# boost.net
KiCad netlist of a schematic drawn in Altium Designer
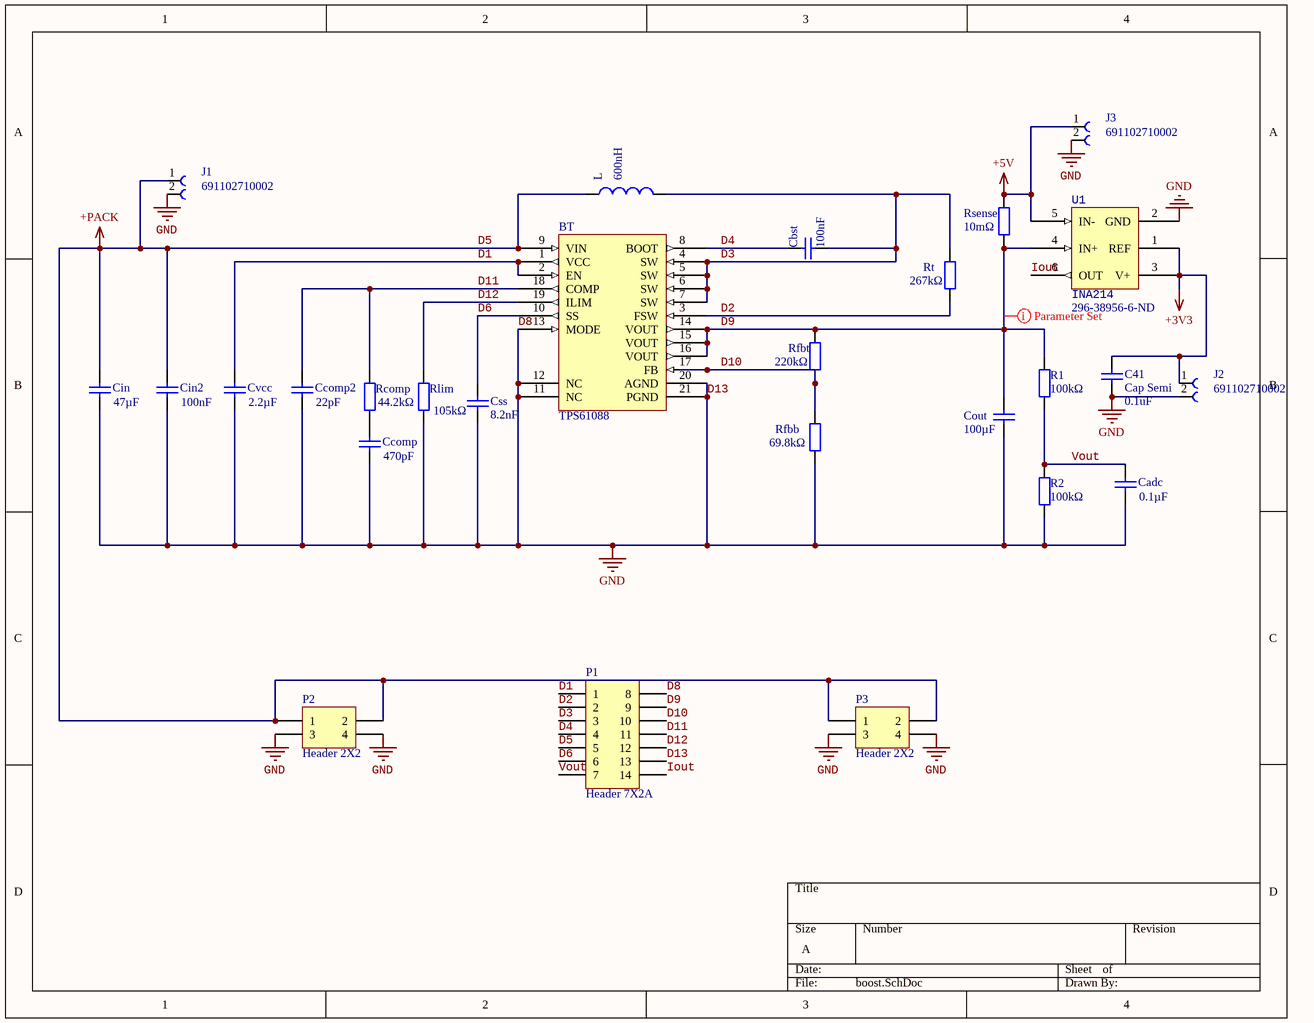
[diagram p0: boost.SchDoc]

(export (version "E")
  (design (tool "Eeschema 10.0.6"))
  (components
    (comp (ref "BT")
      (value "TPS61088")
      (footprint "QFN50P450X350X100-21N")
      (description "Boost converter")
      (libsource (lib "heron-general") (part "TPS61088"))
    )
    (comp (ref "C41")
      (value "Cap Semi")
      (footprint "1608[0603]")
      (description "Capacitor (Semiconductor SIM Model)")
      (fields (field (name "ALTIUM_VALUE") "0.1uF") (field (name "PUBLISHER") "Altium Limited"))
      (libsource (lib "Miscellaneous Devices") (part "Cap Semi"))
    )
    (comp (ref "Cadc")
      (value "0.1µF")
      (footprint "1608[0603]")
      (description "Capacitor")
      (fields (field (name "PUBLISHER") "Altium Limited"))
      (libsource (lib "Miscellaneous Devices") (part "Cap"))
    )
    (comp (ref "Cbst")
      (value "100nF")
      (footprint "1608[0603]")
      (description "Capacitor")
      (fields (field (name "PUBLISHER") "Altium Limited"))
      (libsource (lib "Miscellaneous Devices") (part "Cap"))
    )
    (comp (ref "Ccomp")
      (value "470pF")
      (footprint "1608[0603]")
      (description "Capacitor")
      (fields (field (name "PUBLISHER") "Altium Limited"))
      (libsource (lib "Miscellaneous Devices") (part "Cap"))
    )
    (comp (ref "Ccomp2")
      (value "22pF")
      (footprint "0805")
      (description "Capacitor")
      (fields (field (name "PUBLISHER") "Altium Limited"))
      (libsource (lib "Miscellaneous Devices") (part "Cap"))
    )
    (comp (ref "Cin")
      (value "47µF")
      (footprint "1608[0603]")
      (description "Capacitor")
      (fields (field (name "PUBLISHER") "Altium Limited"))
      (libsource (lib "Miscellaneous Devices") (part "Cap"))
    )
    (comp (ref "Cin2")
      (value "100nF")
      (footprint "1608[0603]")
      (description "Capacitor")
      (fields (field (name "PUBLISHER") "Altium Limited"))
      (libsource (lib "Miscellaneous Devices") (part "Cap"))
    )
    (comp (ref "Cout")
      (value "100µF")
      (footprint "1210")
      (description "Capacitor")
      (fields (field (name "PUBLISHER") "Altium Limited"))
      (libsource (lib "Miscellaneous Devices") (part "Cap"))
    )
    (comp (ref "Css")
      (value "8.2nF")
      (footprint "0805")
      (description "Capacitor")
      (fields (field (name "PUBLISHER") "Altium Limited"))
      (libsource (lib "Miscellaneous Devices") (part "Cap"))
    )
    (comp (ref "Cvcc")
      (value "2.2µF")
      (footprint "0805")
      (description "Capacitor")
      (fields (field (name "PUBLISHER") "Altium Limited"))
      (libsource (lib "Miscellaneous Devices") (part "Cap"))
    )
    (comp (ref "J1")
      (value "691102710002")
      (footprint "691102710002:691102710002")
      (description "102 Series 5mm Pitch Straight, PCB Terminal Block, Through Hole, 2 Way")
      (fields (field (name "MF") "Wurth Electronics"))
      (libsource (lib "691102710002") (part "691102710002"))
    )
    (comp (ref "J2")
      (value "691102710002")
      (footprint "691102710002:691102710002")
      (description "102 Series 5mm Pitch Straight, PCB Terminal Block, Through Hole, 2 Way")
      (fields (field (name "MF") "Wurth Electronics"))
      (libsource (lib "691102710002") (part "691102710002"))
    )
    (comp (ref "J3")
      (value "691102710002")
      (footprint "691102710002:691102710002")
      (description "102 Series 5mm Pitch Straight, PCB Terminal Block, Through Hole, 2 Way")
      (fields (field (name "MF") "Wurth Electronics"))
      (libsource (lib "691102710002") (part "691102710002"))
    )
    (comp (ref "L")
      (value "600nH")
      (footprint "2-SMD")
      (description "Inductor")
      (fields (field (name "PUBLISHER") "Altium Limited"))
      (libsource (lib "Miscellaneous Devices") (part "Inductor"))
    )
    (comp (ref "P1")
      (value "Header 7X2A")
      (footprint "HDR2X7_CEN")
      (description "Header, 7-Pin, Dual row")
      (fields (field (name "PUBLISHER") "Altium Limited"))
      (libsource (lib "Miscellaneous Connectors") (part "Header 7X2A"))
    )
    (comp (ref "P2")
      (value "Header 2X2")
      (footprint "HDR2X2")
      (description "Header, 2-Pin, Dual row")
      (fields (field (name "PUBLISHER") "Altium Limited"))
      (libsource (lib "Miscellaneous Connectors") (part "Header 2X2"))
    )
    (comp (ref "P3")
      (value "Header 2X2")
      (footprint "HDR2X2")
      (description "Header, 2-Pin, Dual row")
      (fields (field (name "PUBLISHER") "Altium Limited"))
      (libsource (lib "Miscellaneous Connectors") (part "Header 2X2"))
    )
    (comp (ref "R1")
      (value "100kΩ")
      (footprint "1608[0603]")
      (description "Resistor")
      (fields (field (name "PUBLISHER") "Altium Limited"))
      (libsource (lib "Miscellaneous Devices") (part "Res2"))
    )
    (comp (ref "R2")
      (value "100kΩ")
      (footprint "1608[0603]")
      (description "Resistor")
      (fields (field (name "PUBLISHER") "Altium Limited"))
      (libsource (lib "Miscellaneous Devices") (part "Res2"))
    )
    (comp (ref "Rcomp")
      (value "44.2kΩ")
      (footprint "0805")
      (description "Resistor")
      (fields (field (name "PUBLISHER") "Altium Limited"))
      (libsource (lib "Miscellaneous Devices") (part "Res2"))
    )
    (comp (ref "Rfbb")
      (value "69.8kΩ")
      (footprint "0805")
      (description "Resistor")
      (fields (field (name "PUBLISHER") "Altium Limited"))
      (libsource (lib "Miscellaneous Devices") (part "Res2"))
    )
    (comp (ref "Rfbt")
      (value "220kΩ")
      (footprint "0805")
      (description "Resistor")
      (fields (field (name "PUBLISHER") "Altium Limited"))
      (libsource (lib "Miscellaneous Devices") (part "Res2"))
    )
    (comp (ref "Rlim")
      (value "105kΩ")
      (footprint "1608[0603]")
      (description "Resistor")
      (fields (field (name "PUBLISHER") "Altium Limited"))
      (libsource (lib "Miscellaneous Devices") (part "Res2"))
    )
    (comp (ref "Rsense")
      (value "10mΩ")
      (footprint "0805")
      (description "Resistor")
      (fields (field (name "Comment") "10mΩ 1/2W 0805") (field (name "PUBLISHER") "Altium Limited"))
      (libsource (lib "Miscellaneous Devices") (part "Res2"))
    )
    (comp (ref "Rt")
      (value "267kΩ")
      (footprint "1608[0603]")
      (description "Resistor")
      (fields (field (name "Comment") "RtA1") (field (name "PUBLISHER") "Altium Limited"))
      (libsource (lib "") (part "Res2_1"))
    )
    (comp (ref "U1")
      (value "INA214")
      (footprint "SOT65P210X110-6N")
      (description "Current monitor")
      (fields (field (name "SUPPLIER PART NUMBER 1") "296-38956-6-ND"))
      (libsource (lib "heron-general") (part "INA214"))
    )
  )
  (nets
    (net (code "1") (name "+3V3") (class "Default")
      (node (ref "C41") (pin "2") (pinfunction "2_2") (pintype "passive"))
      (node (ref "J2") (pin "1") (pinfunction "1_1") (pintype "passive"))
      (node (ref "U1") (pin "1") (pinfunction "REF_1") (pintype "passive"))
      (node (ref "U1") (pin "3") (pinfunction "V+_3") (pintype "power_in"))
    )
    (net (code "2") (name "+5V") (class "Default")
      (node (ref "J3") (pin "1") (pinfunction "1_1") (pintype "passive"))
      (node (ref "Rsense") (pin "2") (pinfunction "2_2") (pintype "passive"))
      (node (ref "U1") (pin "5") (pinfunction "IN-_5") (pintype "input"))
    )
    (net (code "3") (name "+PACK") (class "Default")
      (node (ref "BT") (pin "9") (pinfunction "VIN_9") (pintype "input"))
      (node (ref "Cin") (pin "2") (pinfunction "2_2") (pintype "passive"))
      (node (ref "Cin2") (pin "2") (pinfunction "2_2") (pintype "passive"))
      (node (ref "J1") (pin "1") (pinfunction "1_1") (pintype "passive"))
      (node (ref "L") (pin "1") (pinfunction "1_1") (pintype "passive"))
      (node (ref "P1") (pin "5") (pinfunction "5_5") (pintype "passive"))
      (node (ref "P2") (pin "1") (pinfunction "1_1") (pintype "passive"))
      (node (ref "P2") (pin "2") (pinfunction "2_2") (pintype "passive"))
      (node (ref "P3") (pin "1") (pinfunction "1_1") (pintype "passive"))
      (node (ref "P3") (pin "2") (pinfunction "2_2") (pintype "passive"))
    )
    (net (code "4") (name "/D1") (class "Default")
      (node (ref "BT") (pin "1") (pinfunction "VCC_1") (pintype "output"))
      (node (ref "BT") (pin "2") (pinfunction "EN_2") (pintype "input"))
      (node (ref "Cvcc") (pin "2") (pinfunction "2_2") (pintype "passive"))
      (node (ref "P1") (pin "1") (pinfunction "1_1") (pintype "passive"))
    )
    (net (code "5") (name "/D2") (class "Default")
      (node (ref "BT") (pin "3") (pinfunction "FSW_3") (pintype "input"))
      (node (ref "P1") (pin "2") (pinfunction "2_2") (pintype "passive"))
      (node (ref "Rt") (pin "2") (pinfunction "2_2") (pintype "passive"))
    )
    (net (code "6") (name "/D3") (class "Default")
      (node (ref "BT") (pin "4") (pinfunction "SW_4") (pintype "input"))
      (node (ref "BT") (pin "5") (pinfunction "SW_5") (pintype "input"))
      (node (ref "BT") (pin "6") (pinfunction "SW_6") (pintype "input"))
      (node (ref "BT") (pin "7") (pinfunction "SW_7") (pintype "input"))
      (node (ref "Cbst") (pin "1") (pinfunction "1_1") (pintype "passive"))
      (node (ref "L") (pin "2") (pinfunction "2_2") (pintype "passive"))
      (node (ref "P1") (pin "3") (pinfunction "3_3") (pintype "passive"))
      (node (ref "Rt") (pin "1") (pinfunction "1_1") (pintype "passive"))
    )
    (net (code "7") (name "/D4") (class "Default")
      (node (ref "BT") (pin "8") (pinfunction "BOOT_8") (pintype "output"))
      (node (ref "Cbst") (pin "2") (pinfunction "2_2") (pintype "passive"))
      (node (ref "P1") (pin "4") (pinfunction "4_4") (pintype "passive"))
    )
    (net (code "8") (name "/D6") (class "Default")
      (node (ref "BT") (pin "10") (pinfunction "SS_10") (pintype "output"))
      (node (ref "Css") (pin "2") (pinfunction "2_2") (pintype "passive"))
      (node (ref "P1") (pin "6") (pinfunction "6_6") (pintype "passive"))
    )
    (net (code "9") (name "/D9") (class "Default")
      (node (ref "BT") (pin "14") (pinfunction "VOUT_14") (pintype "output"))
      (node (ref "BT") (pin "15") (pinfunction "VOUT_15") (pintype "output"))
      (node (ref "BT") (pin "16") (pinfunction "VOUT_16") (pintype "output"))
      (node (ref "Cout") (pin "2") (pinfunction "2_2") (pintype "passive"))
      (node (ref "P1") (pin "9") (pinfunction "9_9") (pintype "passive"))
      (node (ref "R1") (pin "2") (pinfunction "2_2") (pintype "passive"))
      (node (ref "Rfbt") (pin "2") (pinfunction "2_2") (pintype "passive"))
      (node (ref "Rsense") (pin "1") (pinfunction "1_1") (pintype "passive"))
      (node (ref "U1") (pin "4") (pinfunction "IN+_4") (pintype "input"))
    )
    (net (code "10") (name "/D10") (class "Default")
      (node (ref "BT") (pin "17") (pinfunction "FB_17") (pintype "input"))
      (node (ref "P1") (pin "10") (pinfunction "10_10") (pintype "passive"))
      (node (ref "Rfbb") (pin "2") (pinfunction "2_2") (pintype "passive"))
      (node (ref "Rfbt") (pin "1") (pinfunction "1_1") (pintype "passive"))
    )
    (net (code "11") (name "/D11") (class "Default")
      (node (ref "BT") (pin "18") (pinfunction "COMP_18") (pintype "output"))
      (node (ref "Ccomp2") (pin "2") (pinfunction "2_2") (pintype "passive"))
      (node (ref "P1") (pin "11") (pinfunction "11_11") (pintype "passive"))
      (node (ref "Rcomp") (pin "2") (pinfunction "2_2") (pintype "passive"))
    )
    (net (code "12") (name "/D12") (class "Default")
      (node (ref "BT") (pin "19") (pinfunction "ILIM_19") (pintype "output"))
      (node (ref "P1") (pin "12") (pinfunction "12_12") (pintype "passive"))
      (node (ref "Rlim") (pin "2") (pinfunction "2_2") (pintype "passive"))
    )
    (net (code "13") (name "/Iout") (class "Default")
      (node (ref "P1") (pin "14") (pinfunction "14_14") (pintype "passive"))
      (node (ref "U1") (pin "6") (pinfunction "OUT_6") (pintype "output"))
    )
    (net (code "14") (name "/Vout") (class "Default")
      (node (ref "Cadc") (pin "1") (pinfunction "1_1") (pintype "passive"))
      (node (ref "P1") (pin "7") (pinfunction "7_7") (pintype "passive"))
      (node (ref "R1") (pin "1") (pinfunction "1_1") (pintype "passive"))
      (node (ref "R2") (pin "2") (pinfunction "2_2") (pintype "passive"))
    )
    (net (code "15") (name "GND") (class "Default")
      (node (ref "BT") (pin "11") (pinfunction "NC_11") (pintype "passive"))
      (node (ref "BT") (pin "12") (pinfunction "NC_12") (pintype "passive"))
      (node (ref "BT") (pin "13") (pinfunction "MODE_13") (pintype "input"))
      (node (ref "BT") (pin "20") (pinfunction "AGND_20") (pintype "power_in"))
      (node (ref "BT") (pin "21") (pinfunction "PGND_21") (pintype "power_in"))
      (node (ref "C41") (pin "1") (pinfunction "1_1") (pintype "passive"))
      (node (ref "Cadc") (pin "2") (pinfunction "2_2") (pintype "passive"))
      (node (ref "Ccomp") (pin "1") (pinfunction "1_1") (pintype "passive"))
      (node (ref "Ccomp2") (pin "1") (pinfunction "1_1") (pintype "passive"))
      (node (ref "Cin") (pin "1") (pinfunction "1_1") (pintype "passive"))
      (node (ref "Cin2") (pin "1") (pinfunction "1_1") (pintype "passive"))
      (node (ref "Cout") (pin "1") (pinfunction "1_1") (pintype "passive"))
      (node (ref "Css") (pin "1") (pinfunction "1_1") (pintype "passive"))
      (node (ref "Cvcc") (pin "1") (pinfunction "1_1") (pintype "passive"))
      (node (ref "J1") (pin "2") (pinfunction "2_2") (pintype "passive"))
      (node (ref "J2") (pin "2") (pinfunction "2_2") (pintype "passive"))
      (node (ref "J3") (pin "2") (pinfunction "2_2") (pintype "passive"))
      (node (ref "P1") (pin "13") (pinfunction "13_13") (pintype "passive"))
      (node (ref "P1") (pin "8") (pinfunction "8_8") (pintype "passive"))
      (node (ref "P2") (pin "3") (pinfunction "3_3") (pintype "passive"))
      (node (ref "P2") (pin "4") (pinfunction "4_4") (pintype "passive"))
      (node (ref "P3") (pin "3") (pinfunction "3_3") (pintype "passive"))
      (node (ref "P3") (pin "4") (pinfunction "4_4") (pintype "passive"))
      (node (ref "R2") (pin "1") (pinfunction "1_1") (pintype "passive"))
      (node (ref "Rfbb") (pin "1") (pinfunction "1_1") (pintype "passive"))
      (node (ref "Rlim") (pin "1") (pinfunction "1_1") (pintype "passive"))
      (node (ref "U1") (pin "2") (pinfunction "GND_2") (pintype "power_in"))
    )
    (net (code "16") (name "Net-(Ccomp-Pad2)") (class "Default")
      (node (ref "Ccomp") (pin "2") (pinfunction "2_2") (pintype "passive"))
      (node (ref "Rcomp") (pin "1") (pinfunction "1_1") (pintype "passive"))
    )
  )
)
